# GridThumbs.net
KiCad netlist of a schematic drawn in EAGLE
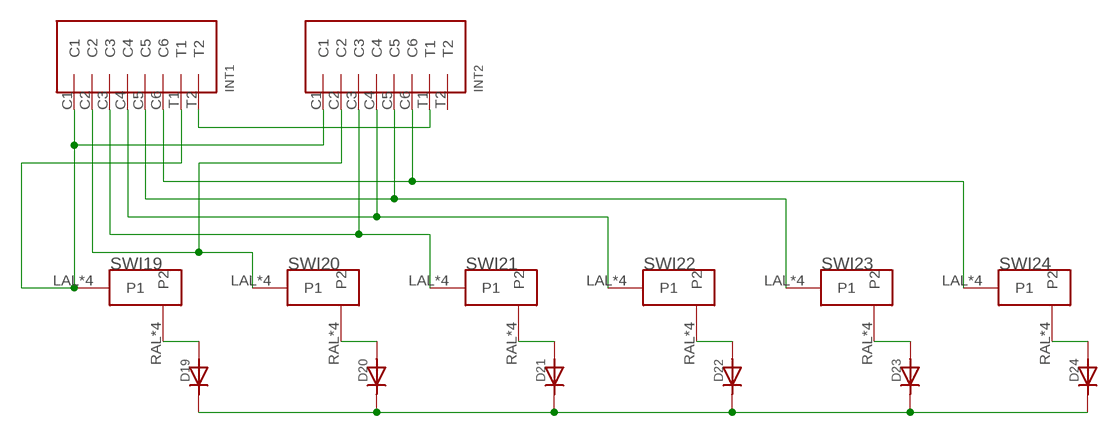
[diagram p0: schematic, sheet 1]

(export (version "E")
  (design (tool "Eeschema 10.0.6"))
  (components
    (comp (ref "D19")
      (value "DIODE")
      (footprint "eagle-import:DIODE_COMBO")
      (libsource (lib "eagle-import") (part "DIODE"))
    )
    (comp (ref "D20")
      (value "DIODE")
      (footprint "eagle-import:DIODE_COMBO")
      (libsource (lib "eagle-import") (part "DIODE"))
    )
    (comp (ref "D21")
      (value "DIODE")
      (footprint "eagle-import:DIODE_COMBO")
      (libsource (lib "eagle-import") (part "DIODE"))
    )
    (comp (ref "D22")
      (value "DIODE")
      (footprint "eagle-import:DIODE_COMBO")
      (libsource (lib "eagle-import") (part "DIODE"))
    )
    (comp (ref "D23")
      (value "DIODE")
      (footprint "eagle-import:DIODE_COMBO")
      (libsource (lib "eagle-import") (part "DIODE"))
    )
    (comp (ref "D24")
      (value "DIODE")
      (footprint "eagle-import:DIODE_COMBO")
      (libsource (lib "eagle-import") (part "DIODE"))
    )
    (comp (ref "INT1")
      (value "INTRCNNT")
      (footprint "eagle-import:INTRCNNT")
      (libsource (lib "eagle-import") (part "INTRCNNT"))
    )
    (comp (ref "INT2")
      (value "INTRCNNT")
      (footprint "eagle-import:INTRCNNT")
      (libsource (lib "eagle-import") (part "INTRCNNT"))
    )
    (comp (ref "SWI19")
      (value "MX/ALPSDOUBLESIDED")
      (footprint "eagle-import:DOUBLED_MX_ALPS")
      (libsource (lib "eagle-import") (part "MX/ALPSDOUBLESIDED"))
    )
    (comp (ref "SWI20")
      (value "MX/ALPSDOUBLESIDED")
      (footprint "eagle-import:DOUBLED_MX_ALPS")
      (libsource (lib "eagle-import") (part "MX/ALPSDOUBLESIDED"))
    )
    (comp (ref "SWI21")
      (value "MX/ALPSDOUBLESIDED")
      (footprint "eagle-import:DOUBLED_MX_ALPS")
      (libsource (lib "eagle-import") (part "MX/ALPSDOUBLESIDED"))
    )
    (comp (ref "SWI22")
      (value "MX/ALPSDOUBLESIDED")
      (footprint "eagle-import:DOUBLED_MX_ALPS")
      (libsource (lib "eagle-import") (part "MX/ALPSDOUBLESIDED"))
    )
    (comp (ref "SWI23")
      (value "MX/ALPSDOUBLESIDED")
      (footprint "eagle-import:DOUBLED_MX_ALPS")
      (libsource (lib "eagle-import") (part "MX/ALPSDOUBLESIDED"))
    )
    (comp (ref "SWI24")
      (value "MX/ALPSDOUBLESIDED")
      (footprint "eagle-import:DOUBLED_MX_ALPS")
      (libsource (lib "eagle-import") (part "MX/ALPSDOUBLESIDED"))
    )
  )
  (nets
    (net (code "1") (name "Net-(D19-AN-PadANOSB)") (class "Default")
      (node (ref "D19") (pin "ANOSB") (pinfunction "AN_ANOSB") (pintype "bidirectional"))
      (node (ref "D19") (pin "ANOST") (pinfunction "AN_ANOST") (pintype "bidirectional"))
      (node (ref "D19") (pin "ANOT") (pinfunction "AN_ANOT") (pintype "bidirectional"))
      (node (ref "SWI19") (pin "RAL") (pinfunction "P2_RAL") (pintype "bidirectional"))
      (node (ref "SWI19") (pin "RAR") (pinfunction "P2_RAR") (pintype "bidirectional"))
      (node (ref "SWI19") (pin "RCL") (pinfunction "P2_RCL") (pintype "bidirectional"))
      (node (ref "SWI19") (pin "RCR") (pinfunction "P2_RCR") (pintype "bidirectional"))
    )
    (net (code "2") (name "Net-(D19-CAT-PadCATSB)") (class "Default")
      (node (ref "D19") (pin "CATSB") (pinfunction "CAT_CATSB") (pintype "bidirectional"))
      (node (ref "D19") (pin "CATST") (pinfunction "CAT_CATST") (pintype "bidirectional"))
      (node (ref "D19") (pin "CATT") (pinfunction "CAT_CATT") (pintype "bidirectional"))
      (node (ref "D20") (pin "CATSB") (pinfunction "CAT_CATSB") (pintype "bidirectional"))
      (node (ref "D20") (pin "CATST") (pinfunction "CAT_CATST") (pintype "bidirectional"))
      (node (ref "D20") (pin "CATT") (pinfunction "CAT_CATT") (pintype "bidirectional"))
      (node (ref "D21") (pin "CATSB") (pinfunction "CAT_CATSB") (pintype "bidirectional"))
      (node (ref "D21") (pin "CATST") (pinfunction "CAT_CATST") (pintype "bidirectional"))
      (node (ref "D21") (pin "CATT") (pinfunction "CAT_CATT") (pintype "bidirectional"))
      (node (ref "D22") (pin "CATSB") (pinfunction "CAT_CATSB") (pintype "bidirectional"))
      (node (ref "D22") (pin "CATST") (pinfunction "CAT_CATST") (pintype "bidirectional"))
      (node (ref "D22") (pin "CATT") (pinfunction "CAT_CATT") (pintype "bidirectional"))
      (node (ref "D23") (pin "CATSB") (pinfunction "CAT_CATSB") (pintype "bidirectional"))
      (node (ref "D23") (pin "CATST") (pinfunction "CAT_CATST") (pintype "bidirectional"))
      (node (ref "D23") (pin "CATT") (pinfunction "CAT_CATT") (pintype "bidirectional"))
      (node (ref "D24") (pin "CATSB") (pinfunction "CAT_CATSB") (pintype "bidirectional"))
      (node (ref "D24") (pin "CATST") (pinfunction "CAT_CATST") (pintype "bidirectional"))
      (node (ref "D24") (pin "CATT") (pinfunction "CAT_CATT") (pintype "bidirectional"))
    )
    (net (code "3") (name "Net-(D20-AN-PadANOSB)") (class "Default")
      (node (ref "D20") (pin "ANOSB") (pinfunction "AN_ANOSB") (pintype "bidirectional"))
      (node (ref "D20") (pin "ANOST") (pinfunction "AN_ANOST") (pintype "bidirectional"))
      (node (ref "D20") (pin "ANOT") (pinfunction "AN_ANOT") (pintype "bidirectional"))
      (node (ref "SWI20") (pin "RAL") (pinfunction "P2_RAL") (pintype "bidirectional"))
      (node (ref "SWI20") (pin "RAR") (pinfunction "P2_RAR") (pintype "bidirectional"))
      (node (ref "SWI20") (pin "RCL") (pinfunction "P2_RCL") (pintype "bidirectional"))
      (node (ref "SWI20") (pin "RCR") (pinfunction "P2_RCR") (pintype "bidirectional"))
    )
    (net (code "4") (name "Net-(D21-AN-PadANOSB)") (class "Default")
      (node (ref "D21") (pin "ANOSB") (pinfunction "AN_ANOSB") (pintype "bidirectional"))
      (node (ref "D21") (pin "ANOST") (pinfunction "AN_ANOST") (pintype "bidirectional"))
      (node (ref "D21") (pin "ANOT") (pinfunction "AN_ANOT") (pintype "bidirectional"))
      (node (ref "SWI21") (pin "RAL") (pinfunction "P2_RAL") (pintype "bidirectional"))
      (node (ref "SWI21") (pin "RAR") (pinfunction "P2_RAR") (pintype "bidirectional"))
      (node (ref "SWI21") (pin "RCL") (pinfunction "P2_RCL") (pintype "bidirectional"))
      (node (ref "SWI21") (pin "RCR") (pinfunction "P2_RCR") (pintype "bidirectional"))
    )
    (net (code "5") (name "Net-(D22-AN-PadANOSB)") (class "Default")
      (node (ref "D22") (pin "ANOSB") (pinfunction "AN_ANOSB") (pintype "bidirectional"))
      (node (ref "D22") (pin "ANOST") (pinfunction "AN_ANOST") (pintype "bidirectional"))
      (node (ref "D22") (pin "ANOT") (pinfunction "AN_ANOT") (pintype "bidirectional"))
      (node (ref "SWI22") (pin "RAL") (pinfunction "P2_RAL") (pintype "bidirectional"))
      (node (ref "SWI22") (pin "RAR") (pinfunction "P2_RAR") (pintype "bidirectional"))
      (node (ref "SWI22") (pin "RCL") (pinfunction "P2_RCL") (pintype "bidirectional"))
      (node (ref "SWI22") (pin "RCR") (pinfunction "P2_RCR") (pintype "bidirectional"))
    )
    (net (code "6") (name "Net-(D23-AN-PadANOSB)") (class "Default")
      (node (ref "D23") (pin "ANOSB") (pinfunction "AN_ANOSB") (pintype "bidirectional"))
      (node (ref "D23") (pin "ANOST") (pinfunction "AN_ANOST") (pintype "bidirectional"))
      (node (ref "D23") (pin "ANOT") (pinfunction "AN_ANOT") (pintype "bidirectional"))
      (node (ref "SWI23") (pin "RAL") (pinfunction "P2_RAL") (pintype "bidirectional"))
      (node (ref "SWI23") (pin "RAR") (pinfunction "P2_RAR") (pintype "bidirectional"))
      (node (ref "SWI23") (pin "RCL") (pinfunction "P2_RCL") (pintype "bidirectional"))
      (node (ref "SWI23") (pin "RCR") (pinfunction "P2_RCR") (pintype "bidirectional"))
    )
    (net (code "7") (name "Net-(D24-AN-PadANOSB)") (class "Default")
      (node (ref "D24") (pin "ANOSB") (pinfunction "AN_ANOSB") (pintype "bidirectional"))
      (node (ref "D24") (pin "ANOST") (pinfunction "AN_ANOST") (pintype "bidirectional"))
      (node (ref "D24") (pin "ANOT") (pinfunction "AN_ANOT") (pintype "bidirectional"))
      (node (ref "SWI24") (pin "RAL") (pinfunction "P2_RAL") (pintype "bidirectional"))
      (node (ref "SWI24") (pin "RAR") (pinfunction "P2_RAR") (pintype "bidirectional"))
      (node (ref "SWI24") (pin "RCL") (pinfunction "P2_RCL") (pintype "bidirectional"))
      (node (ref "SWI24") (pin "RCR") (pinfunction "P2_RCR") (pintype "bidirectional"))
    )
    (net (code "8") (name "Net-(INT1-PadC1)") (class "Default")
      (node (ref "INT1") (pin "C1") (pinfunction "C1_C1") (pintype "bidirectional"))
      (node (ref "INT1") (pin "T1") (pinfunction "T1_T1") (pintype "bidirectional"))
      (node (ref "INT2") (pin "C1") (pinfunction "C1_C1") (pintype "bidirectional"))
      (node (ref "SWI19") (pin "LAL") (pinfunction "P1_LAL") (pintype "bidirectional"))
      (node (ref "SWI19") (pin "LAR") (pinfunction "P1_LAR") (pintype "bidirectional"))
      (node (ref "SWI19") (pin "LCL") (pinfunction "P1_LCL") (pintype "bidirectional"))
      (node (ref "SWI19") (pin "LCR") (pinfunction "P1_LCR") (pintype "bidirectional"))
    )
    (net (code "9") (name "Net-(INT1-PadC2)") (class "Default")
      (node (ref "INT1") (pin "C2") (pinfunction "C2_C2") (pintype "bidirectional"))
      (node (ref "INT2") (pin "C2") (pinfunction "C2_C2") (pintype "bidirectional"))
      (node (ref "SWI20") (pin "LAL") (pinfunction "P1_LAL") (pintype "bidirectional"))
      (node (ref "SWI20") (pin "LAR") (pinfunction "P1_LAR") (pintype "bidirectional"))
      (node (ref "SWI20") (pin "LCL") (pinfunction "P1_LCL") (pintype "bidirectional"))
      (node (ref "SWI20") (pin "LCR") (pinfunction "P1_LCR") (pintype "bidirectional"))
    )
    (net (code "10") (name "Net-(INT1-PadC3)") (class "Default")
      (node (ref "INT1") (pin "C3") (pinfunction "C3_C3") (pintype "bidirectional"))
      (node (ref "INT2") (pin "C3") (pinfunction "C3_C3") (pintype "bidirectional"))
      (node (ref "SWI21") (pin "LAL") (pinfunction "P1_LAL") (pintype "bidirectional"))
      (node (ref "SWI21") (pin "LAR") (pinfunction "P1_LAR") (pintype "bidirectional"))
      (node (ref "SWI21") (pin "LCL") (pinfunction "P1_LCL") (pintype "bidirectional"))
      (node (ref "SWI21") (pin "LCR") (pinfunction "P1_LCR") (pintype "bidirectional"))
    )
    (net (code "11") (name "Net-(INT1-PadC4)") (class "Default")
      (node (ref "INT1") (pin "C4") (pinfunction "C4_C4") (pintype "bidirectional"))
      (node (ref "INT2") (pin "C4") (pinfunction "C4_C4") (pintype "bidirectional"))
      (node (ref "SWI22") (pin "LAL") (pinfunction "P1_LAL") (pintype "bidirectional"))
      (node (ref "SWI22") (pin "LAR") (pinfunction "P1_LAR") (pintype "bidirectional"))
      (node (ref "SWI22") (pin "LCL") (pinfunction "P1_LCL") (pintype "bidirectional"))
      (node (ref "SWI22") (pin "LCR") (pinfunction "P1_LCR") (pintype "bidirectional"))
    )
    (net (code "12") (name "Net-(INT1-PadC5)") (class "Default")
      (node (ref "INT1") (pin "C5") (pinfunction "C5_C5") (pintype "bidirectional"))
      (node (ref "INT2") (pin "C5") (pinfunction "C5_C5") (pintype "bidirectional"))
      (node (ref "SWI23") (pin "LAL") (pinfunction "P1_LAL") (pintype "bidirectional"))
      (node (ref "SWI23") (pin "LAR") (pinfunction "P1_LAR") (pintype "bidirectional"))
      (node (ref "SWI23") (pin "LCL") (pinfunction "P1_LCL") (pintype "bidirectional"))
      (node (ref "SWI23") (pin "LCR") (pinfunction "P1_LCR") (pintype "bidirectional"))
    )
    (net (code "13") (name "Net-(INT1-PadC6)") (class "Default")
      (node (ref "INT1") (pin "C6") (pinfunction "C6_C6") (pintype "bidirectional"))
      (node (ref "INT2") (pin "C6") (pinfunction "C6_C6") (pintype "bidirectional"))
      (node (ref "SWI24") (pin "LAL") (pinfunction "P1_LAL") (pintype "bidirectional"))
      (node (ref "SWI24") (pin "LAR") (pinfunction "P1_LAR") (pintype "bidirectional"))
      (node (ref "SWI24") (pin "LCL") (pinfunction "P1_LCL") (pintype "bidirectional"))
      (node (ref "SWI24") (pin "LCR") (pinfunction "P1_LCR") (pintype "bidirectional"))
    )
    (net (code "14") (name "Net-(INT1-PadT2)") (class "Default")
      (node (ref "INT1") (pin "T2") (pinfunction "T2_T2") (pintype "bidirectional"))
      (node (ref "INT2") (pin "T1") (pinfunction "T1_T1") (pintype "bidirectional"))
    )
    (net (code "15") (name "unconnected-(INT2-PadT2)") (class "Default")
      (node (ref "INT2") (pin "T2") (pinfunction "T2_T2") (pintype "bidirectional"))
    )
  )
)
